# 32u4_denemesi.net
KiCad netlist of a schematic drawn in EAGLE
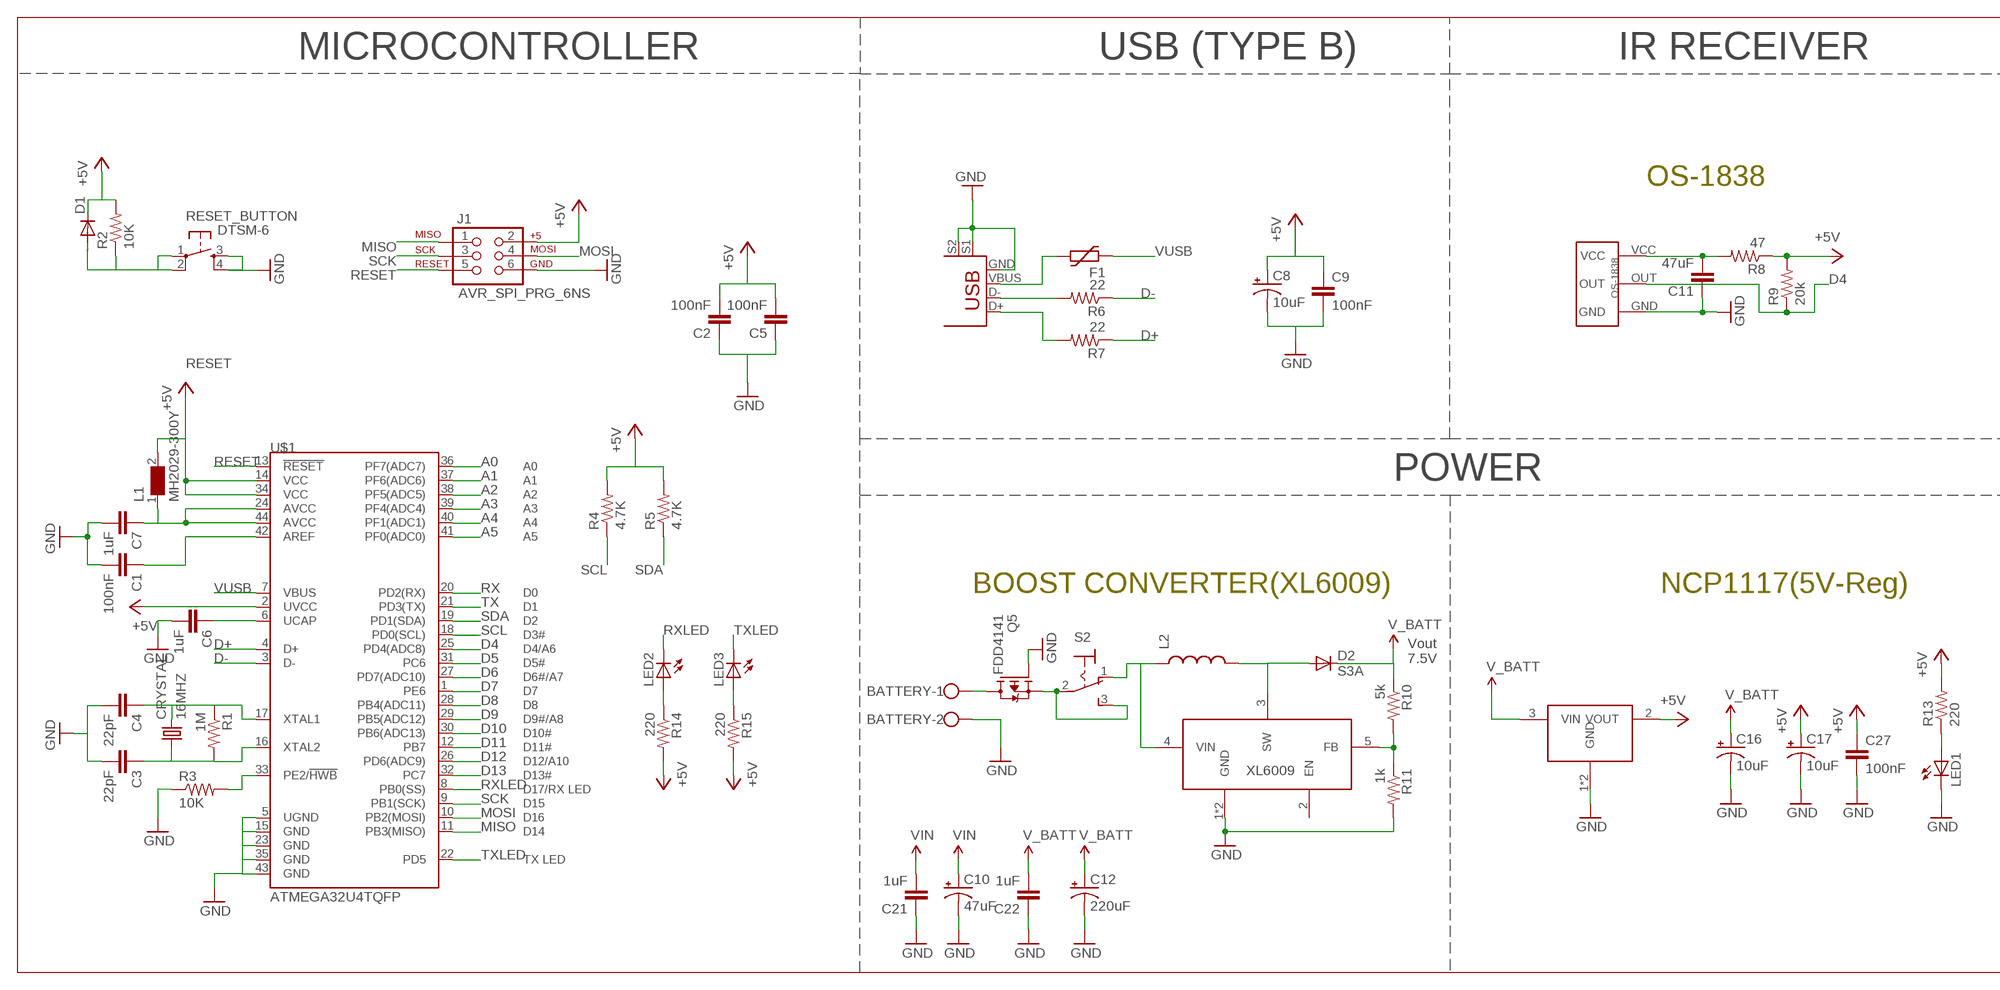
[diagram p0: schematic, sheet 1, part 1 of 2]
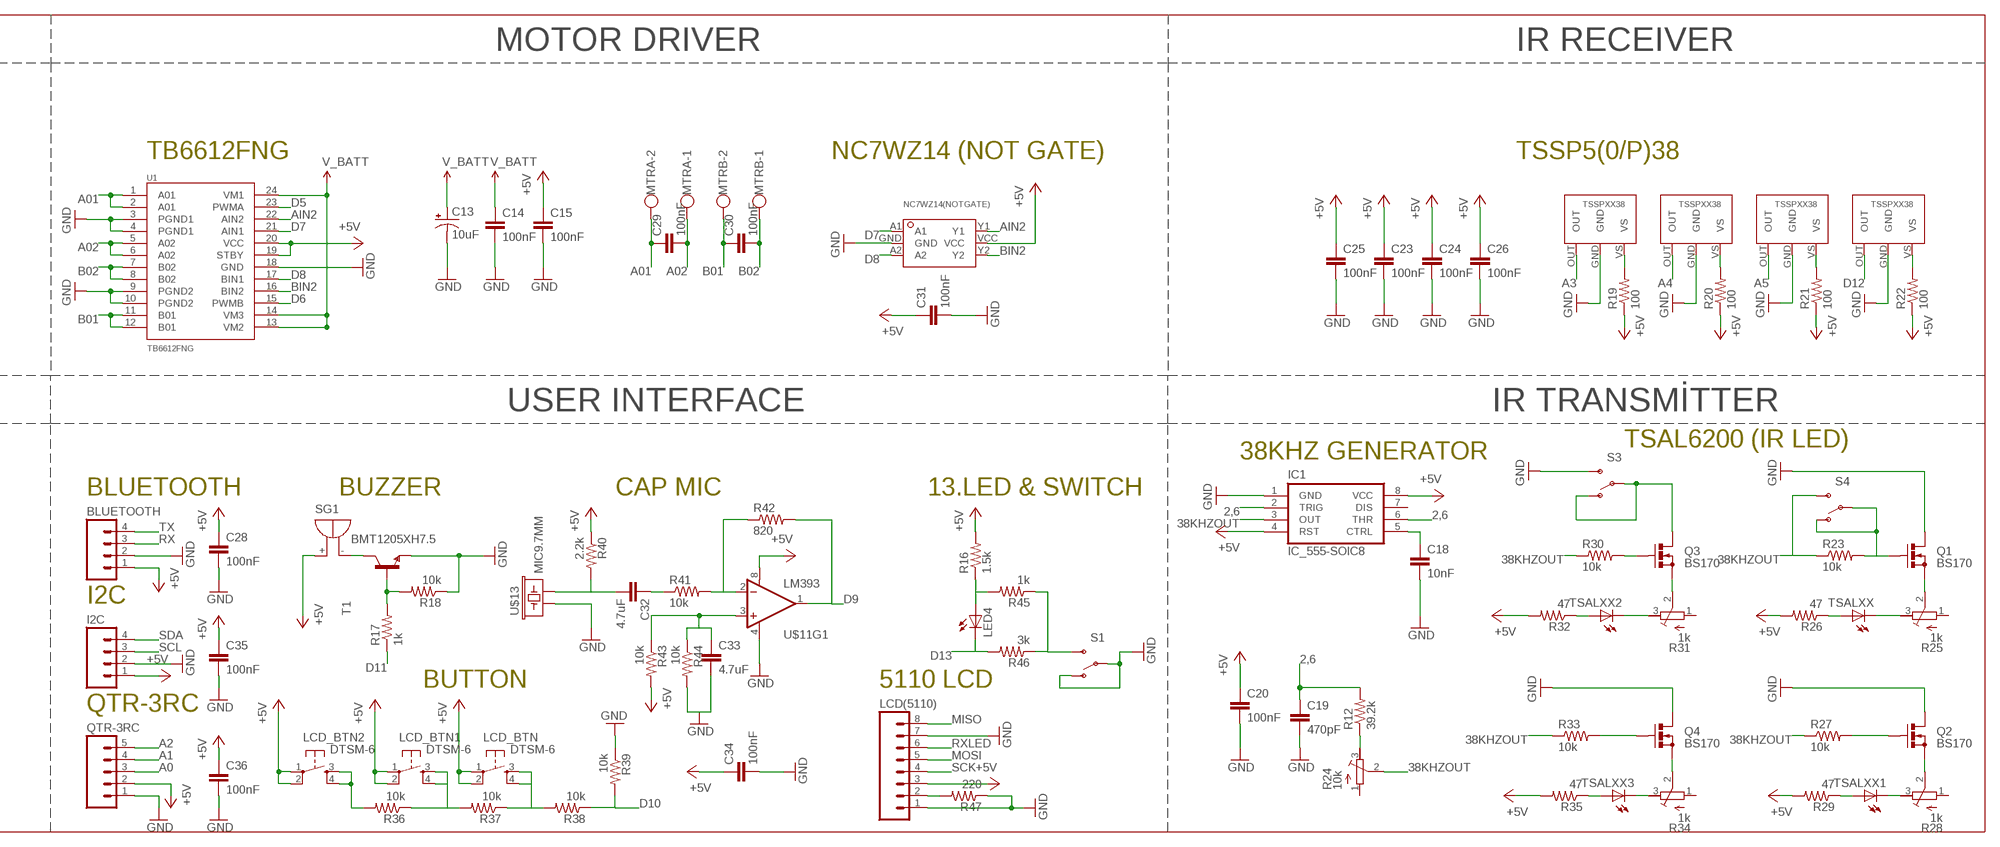
[diagram p1: schematic, sheet 1, part 2 of 2]

(export (version "E")
  (design (tool "Eeschema 10.0.6"))
  (components
    (comp (ref "BATTERY")
      (value "W237-102")
      (footprint "eagle-import:W237-102")
      (fields (field (name "MPN") "237-102"))
      (libsource (lib "eagle-import") (part "W237-102"))
    )
    (comp (ref "BLUETOOTH")
      (value "M04PTH")
      (footprint "eagle-import:1X04")
      (libsource (lib "eagle-import") (part "M04PTH"))
    )
    (comp (ref "C1")
      (value "100nF")
      (footprint "eagle-import:0805")
      (libsource (lib "eagle-import") (part "CAP0805"))
    )
    (comp (ref "C2")
      (value "100nF")
      (footprint "eagle-import:0805")
      (libsource (lib "eagle-import") (part "CAP0805"))
    )
    (comp (ref "C3")
      (value "22pF")
      (footprint "eagle-import:0805")
      (libsource (lib "eagle-import") (part "CAP0805"))
    )
    (comp (ref "C4")
      (value "22pF")
      (footprint "eagle-import:0805")
      (libsource (lib "eagle-import") (part "CAP0805"))
    )
    (comp (ref "C5")
      (value "100nF")
      (footprint "eagle-import:0805")
      (libsource (lib "eagle-import") (part "CAP0805"))
    )
    (comp (ref "C6")
      (value "1uF")
      (footprint "eagle-import:1206")
      (libsource (lib "eagle-import") (part "CAP1206"))
    )
    (comp (ref "C7")
      (value "1uF")
      (footprint "eagle-import:1206")
      (libsource (lib "eagle-import") (part "CAP1206"))
    )
    (comp (ref "C8")
      (value "10uF")
      (footprint "eagle-import:EIA3216")
      (libsource (lib "eagle-import") (part "CAP_POL1206"))
    )
    (comp (ref "C9")
      (value "100nF")
      (footprint "eagle-import:0805")
      (libsource (lib "eagle-import") (part "CAP0805"))
    )
    (comp (ref "C10")
      (value "47uF")
      (footprint "eagle-import:NIPPON_F80")
      (libsource (lib "eagle-import") (part "SparkFun-Passives_CAP_POLF80"))
    )
    (comp (ref "C11")
      (value "47uF")
      (footprint "eagle-import:1206")
      (libsource (lib "eagle-import") (part "CAP1206"))
    )
    (comp (ref "C12")
      (value "220uF")
      (footprint "eagle-import:PANASONIC_G")
      (libsource (lib "eagle-import") (part "SparkFun-Passives_CAP_POLG"))
    )
    (comp (ref "C13")
      (value "10uF")
      (footprint "eagle-import:EIA3528")
      (libsource (lib "eagle-import") (part "CAP_POL3528"))
    )
    (comp (ref "C14")
      (value "100nF")
      (footprint "eagle-import:0805")
      (libsource (lib "eagle-import") (part "CAP0805"))
    )
    (comp (ref "C15")
      (value "100nF")
      (footprint "eagle-import:0805")
      (libsource (lib "eagle-import") (part "CAP0805"))
    )
    (comp (ref "C16")
      (value "10uF")
      (footprint "eagle-import:EIA3216")
      (libsource (lib "eagle-import") (part "CAP_POL1206"))
    )
    (comp (ref "C17")
      (value "10uF")
      (footprint "eagle-import:EIA3216")
      (libsource (lib "eagle-import") (part "CAP_POL1206"))
    )
    (comp (ref "C18")
      (value "10nF")
      (footprint "eagle-import:0805")
      (libsource (lib "eagle-import") (part "CAP0805"))
    )
    (comp (ref "C19")
      (value "470pF")
      (footprint "eagle-import:0805")
      (libsource (lib "eagle-import") (part "CAP0805"))
    )
    (comp (ref "C20")
      (value "100nF")
      (footprint "eagle-import:0805")
      (libsource (lib "eagle-import") (part "CAP0805"))
    )
    (comp (ref "C21")
      (value "1uF")
      (footprint "eagle-import:1206")
      (libsource (lib "eagle-import") (part "CAP1206"))
    )
    (comp (ref "C22")
      (value "1uF")
      (footprint "eagle-import:1206")
      (libsource (lib "eagle-import") (part "CAP1206"))
    )
    (comp (ref "C23")
      (value "100nF")
      (footprint "eagle-import:0805")
      (libsource (lib "eagle-import") (part "CAP0805"))
    )
    (comp (ref "C24")
      (value "100nF")
      (footprint "eagle-import:0805")
      (libsource (lib "eagle-import") (part "CAP0805"))
    )
    (comp (ref "C25")
      (value "100nF")
      (footprint "eagle-import:0805")
      (libsource (lib "eagle-import") (part "CAP0805"))
    )
    (comp (ref "C26")
      (value "100nF")
      (footprint "eagle-import:0805")
      (libsource (lib "eagle-import") (part "CAP0805"))
    )
    (comp (ref "C27")
      (value "100nF")
      (footprint "eagle-import:0805")
      (libsource (lib "eagle-import") (part "CAP0805"))
    )
    (comp (ref "C28")
      (value "100nF")
      (footprint "eagle-import:0805")
      (libsource (lib "eagle-import") (part "CAP0805"))
    )
    (comp (ref "C29")
      (value "100nF")
      (footprint "eagle-import:0805")
      (libsource (lib "eagle-import") (part "CAP0805"))
    )
    (comp (ref "C30")
      (value "100nF")
      (footprint "eagle-import:0805")
      (libsource (lib "eagle-import") (part "CAP0805"))
    )
    (comp (ref "C31")
      (value "100nF")
      (footprint "eagle-import:0805")
      (libsource (lib "eagle-import") (part "CAP0805"))
    )
    (comp (ref "C32")
      (value "4.7uF")
      (footprint "eagle-import:1206")
      (libsource (lib "eagle-import") (part "CAP1206"))
    )
    (comp (ref "C33")
      (value "4.7uF")
      (footprint "eagle-import:1206")
      (libsource (lib "eagle-import") (part "CAP1206"))
    )
    (comp (ref "C34")
      (value "100nF")
      (footprint "eagle-import:0805")
      (libsource (lib "eagle-import") (part "CAP0805"))
    )
    (comp (ref "C35")
      (value "100nF")
      (footprint "eagle-import:0805")
      (libsource (lib "eagle-import") (part "CAP0805"))
    )
    (comp (ref "C36")
      (value "100nF")
      (footprint "eagle-import:0805")
      (libsource (lib "eagle-import") (part "CAP0805"))
    )
    (comp (ref "CRYSTAL")
      (value "16MHZ")
      (footprint "eagle-import:CRYSTAL-SMD-5X3")
      (libsource (lib "eagle-import") (part "CRYSTAL5X3"))
    )
    (comp (ref "D1")
      (value "DIODE-MINIMELF")
      (footprint "eagle-import:MINIMELF")
      (libsource (lib "eagle-import") (part "DIODE-MINIMELF"))
    )
    (comp (ref "D2")
      (value "S3A")
      (footprint "eagle-import:DO214AB")
      (fields (field (name "MF") "Fairchild"))
      (libsource (lib "eagle-import") (part "S3A"))
    )
    (comp (ref "F1")
      (value "FUSE_PTC-0805")
      (footprint "eagle-import:PTC0805")
      (libsource (lib "eagle-import") (part "FUSE_PTC-0805"))
    )
    (comp (ref "I2C")
      (value "M04PTH")
      (footprint "eagle-import:1X04")
      (libsource (lib "eagle-import") (part "M04PTH"))
    )
    (comp (ref "IC1")
      (value "IC_555-SOIC8")
      (footprint "eagle-import:SOIC-8")
      (libsource (lib "eagle-import") (part "IC_555-SOIC8"))
    )
    (comp (ref "J1")
      (value "AVR_SPI_PRG_6NS")
      (footprint "eagle-import:2X3-NS")
      (libsource (lib "eagle-import") (part "AVR_SPI_PRG_6NS"))
    )
    (comp (ref "L1")
      (value "MH2029-300Y")
      (footprint "eagle-import:0805")
      (libsource (lib "eagle-import") (part "WE-CBF_0805"))
    )
    (comp (ref "L2")
      (value "INDUCTORPWR")
      (footprint "eagle-import:CDRH125")
      (libsource (lib "eagle-import") (part "INDUCTORPWR"))
    )
    (comp (ref "LCD(5110)")
      (value "M081X08")
      (footprint "eagle-import:1X08")
      (libsource (lib "eagle-import") (part "M081X08"))
    )
    (comp (ref "LCD_BTN")
      (value "DTSM-6")
      (footprint "eagle-import:DTSM-6")
      (libsource (lib "eagle-import") (part "DTSM-6"))
    )
    (comp (ref "LCD_BTN1")
      (value "DTSM-6")
      (footprint "eagle-import:DTSM-6")
      (libsource (lib "eagle-import") (part "DTSM-6"))
    )
    (comp (ref "LCD_BTN2")
      (value "DTSM-6")
      (footprint "eagle-import:DTSM-6")
      (libsource (lib "eagle-import") (part "DTSM-6"))
    )
    (comp (ref "LED1")
      (value "LEDCHIPLED_0805")
      (footprint "eagle-import:CHIPLED_0805")
      (libsource (lib "eagle-import") (part "LEDCHIPLED_0805"))
    )
    (comp (ref "LED2")
      (value "LEDCHIPLED_0805")
      (footprint "eagle-import:CHIPLED_0805")
      (libsource (lib "eagle-import") (part "LEDCHIPLED_0805"))
    )
    (comp (ref "LED3")
      (value "LEDCHIPLED_0805")
      (footprint "eagle-import:CHIPLED_0805")
      (libsource (lib "eagle-import") (part "LEDCHIPLED_0805"))
    )
    (comp (ref "LED4")
      (value "LEDCHIPLED_0805")
      (footprint "eagle-import:CHIPLED_0805")
      (libsource (lib "eagle-import") (part "LEDCHIPLED_0805"))
    )
    (comp (ref "MTRA")
      (value "W237-102")
      (footprint "eagle-import:W237-102")
      (fields (field (name "MPN") "237-102"))
      (libsource (lib "eagle-import") (part "W237-102"))
    )
    (comp (ref "MTRB")
      (value "W237-102")
      (footprint "eagle-import:W237-102")
      (fields (field (name "MPN") "237-102"))
      (libsource (lib "eagle-import") (part "W237-102"))
    )
    (comp (ref "Q1")
      (value "BS170")
      (footprint "eagle-import:SOT54ES")
      (libsource (lib "eagle-import") (part "BS170"))
    )
    (comp (ref "Q2")
      (value "BS170")
      (footprint "eagle-import:SOT54ES")
      (libsource (lib "eagle-import") (part "BS170"))
    )
    (comp (ref "Q3")
      (value "BS170")
      (footprint "eagle-import:SOT54ES")
      (libsource (lib "eagle-import") (part "BS170"))
    )
    (comp (ref "Q4")
      (value "BS170")
      (footprint "eagle-import:SOT54ES")
      (libsource (lib "eagle-import") (part "BS170"))
    )
    (comp (ref "Q5")
      (value "FDD4141")
      (footprint "eagle-import:TO252")
      (libsource (lib "eagle-import") (part "FDD4141TO252"))
    )
    (comp (ref "QTR-3RC")
      (value "M05PTH")
      (footprint "eagle-import:1X05")
      (libsource (lib "eagle-import") (part "M05PTH"))
    )
    (comp (ref "R1")
      (value "1M")
      (footprint "eagle-import:0805")
      (libsource (lib "eagle-import") (part "SparkFun-Resistors_RESISTOR0805-RES"))
    )
    (comp (ref "R2")
      (value "10K")
      (footprint "eagle-import:0805")
      (libsource (lib "eagle-import") (part "SparkFun-Resistors_RESISTOR0805-RES"))
    )
    (comp (ref "R3")
      (value "10K")
      (footprint "eagle-import:0805")
      (libsource (lib "eagle-import") (part "SparkFun-Resistors_RESISTOR0805-RES"))
    )
    (comp (ref "R4")
      (value "4.7K")
      (footprint "eagle-import:0805")
      (libsource (lib "eagle-import") (part "SparkFun-Resistors_RESISTOR0805-RES"))
    )
    (comp (ref "R5")
      (value "4.7K")
      (footprint "eagle-import:0805")
      (libsource (lib "eagle-import") (part "SparkFun-Resistors_RESISTOR0805-RES"))
    )
    (comp (ref "R6")
      (value "22")
      (footprint "eagle-import:0805")
      (libsource (lib "eagle-import") (part "SparkFun-Resistors_RESISTOR0805-RES"))
    )
    (comp (ref "R7")
      (value "22")
      (footprint "eagle-import:0805")
      (libsource (lib "eagle-import") (part "SparkFun-Resistors_RESISTOR0805-RES"))
    )
    (comp (ref "R8")
      (value "47")
      (footprint "eagle-import:0805")
      (libsource (lib "eagle-import") (part "SparkFun-Resistors_RESISTOR0805-RES"))
    )
    (comp (ref "R9")
      (value "20k")
      (footprint "eagle-import:0805")
      (libsource (lib "eagle-import") (part "SparkFun-Resistors_RESISTOR0805-RES"))
    )
    (comp (ref "R10")
      (value "5k")
      (footprint "eagle-import:0805")
      (libsource (lib "eagle-import") (part "SparkFun-Resistors_RESISTOR0805-RES"))
    )
    (comp (ref "R11")
      (value "1k")
      (footprint "eagle-import:0805")
      (libsource (lib "eagle-import") (part "SparkFun-Resistors_RESISTOR0805-RES"))
    )
    (comp (ref "R12")
      (value "39.2k")
      (footprint "eagle-import:0402-RES")
      (libsource (lib "eagle-import") (part "RESISTOR0402-RES"))
    )
    (comp (ref "R13")
      (value "220")
      (footprint "eagle-import:0805")
      (libsource (lib "eagle-import") (part "SparkFun-Resistors_RESISTOR0805-RES"))
    )
    (comp (ref "R14")
      (value "220")
      (footprint "eagle-import:0805")
      (libsource (lib "eagle-import") (part "SparkFun-Resistors_RESISTOR0805-RES"))
    )
    (comp (ref "R15")
      (value "220")
      (footprint "eagle-import:0805")
      (libsource (lib "eagle-import") (part "SparkFun-Resistors_RESISTOR0805-RES"))
    )
    (comp (ref "R16")
      (value "1.5k")
      (footprint "eagle-import:0805")
      (libsource (lib "eagle-import") (part "SparkFun-Resistors_RESISTOR0805-RES"))
    )
    (comp (ref "R17")
      (value "1k")
      (footprint "eagle-import:0805")
      (libsource (lib "eagle-import") (part "SparkFun-Resistors_RESISTOR0805-RES"))
    )
    (comp (ref "R18")
      (value "10k")
      (footprint "eagle-import:0805")
      (libsource (lib "eagle-import") (part "SparkFun-Resistors_RESISTOR0805-RES"))
    )
    (comp (ref "R19")
      (value "100")
      (footprint "eagle-import:0805")
      (libsource (lib "eagle-import") (part "SparkFun-Resistors_RESISTOR0805-RES"))
    )
    (comp (ref "R20")
      (value "100")
      (footprint "eagle-import:0805")
      (libsource (lib "eagle-import") (part "SparkFun-Resistors_RESISTOR0805-RES"))
    )
    (comp (ref "R21")
      (value "100")
      (footprint "eagle-import:0805")
      (libsource (lib "eagle-import") (part "SparkFun-Resistors_RESISTOR0805-RES"))
    )
    (comp (ref "R22")
      (value "100")
      (footprint "eagle-import:0805")
      (libsource (lib "eagle-import") (part "SparkFun-Resistors_RESISTOR0805-RES"))
    )
    (comp (ref "R23")
      (value "10k")
      (footprint "eagle-import:0402-RES")
      (libsource (lib "eagle-import") (part "RESISTOR0402-RES"))
    )
    (comp (ref "R24")
      (value "10k")
      (footprint "eagle-import:RTRIM3296W")
      (libsource (lib "eagle-import") (part "R-TRIMM3296W"))
    )
    (comp (ref "R25")
      (value "1k")
      (footprint "eagle-import:RTRIM3296W")
      (libsource (lib "eagle-import") (part "R-TRIMM3296W"))
    )
    (comp (ref "R26")
      (value "47")
      (footprint "eagle-import:0402-RES")
      (libsource (lib "eagle-import") (part "RESISTOR0402-RES"))
    )
    (comp (ref "R27")
      (value "10k")
      (footprint "eagle-import:0402-RES")
      (libsource (lib "eagle-import") (part "RESISTOR0402-RES"))
    )
    (comp (ref "R28")
      (value "1k")
      (footprint "eagle-import:RTRIM3296W")
      (libsource (lib "eagle-import") (part "R-TRIMM3296W"))
    )
    (comp (ref "R29")
      (value "47")
      (footprint "eagle-import:0402-RES")
      (libsource (lib "eagle-import") (part "RESISTOR0402-RES"))
    )
    (comp (ref "R30")
      (value "10k")
      (footprint "eagle-import:0402-RES")
      (libsource (lib "eagle-import") (part "RESISTOR0402-RES"))
    )
    (comp (ref "R31")
      (value "1k")
      (footprint "eagle-import:RTRIM3296W")
      (libsource (lib "eagle-import") (part "R-TRIMM3296W"))
    )
    (comp (ref "R32")
      (value "47")
      (footprint "eagle-import:0402-RES")
      (libsource (lib "eagle-import") (part "RESISTOR0402-RES"))
    )
    (comp (ref "R33")
      (value "10k")
      (footprint "eagle-import:0402-RES")
      (libsource (lib "eagle-import") (part "RESISTOR0402-RES"))
    )
    (comp (ref "R34")
      (value "1k")
      (footprint "eagle-import:RTRIM3296W")
      (libsource (lib "eagle-import") (part "R-TRIMM3296W"))
    )
    (comp (ref "R35")
      (value "47")
      (footprint "eagle-import:0402-RES")
      (libsource (lib "eagle-import") (part "RESISTOR0402-RES"))
    )
    (comp (ref "R36")
      (value "10k")
      (footprint "eagle-import:0805")
      (libsource (lib "eagle-import") (part "SparkFun-Resistors_RESISTOR0805-RES"))
    )
    (comp (ref "R37")
      (value "10k")
      (footprint "eagle-import:0805")
      (libsource (lib "eagle-import") (part "SparkFun-Resistors_RESISTOR0805-RES"))
    )
    (comp (ref "R38")
      (value "10k")
      (footprint "eagle-import:0805")
      (libsource (lib "eagle-import") (part "SparkFun-Resistors_RESISTOR0805-RES"))
    )
    (comp (ref "R39")
      (value "10k")
      (footprint "eagle-import:0805")
      (libsource (lib "eagle-import") (part "SparkFun-Resistors_RESISTOR0805-RES"))
    )
    (comp (ref "R40")
      (value "2.2k")
      (footprint "eagle-import:0805")
      (libsource (lib "eagle-import") (part "SparkFun-Resistors_RESISTOR0805-RES"))
    )
    (comp (ref "R41")
      (value "10k")
      (footprint "eagle-import:0805")
      (libsource (lib "eagle-import") (part "SparkFun-Resistors_RESISTOR0805-RES"))
    )
    (comp (ref "R42")
      (value "820")
      (footprint "eagle-import:0805")
      (libsource (lib "eagle-import") (part "SparkFun-Resistors_RESISTOR0805-RES"))
    )
    (comp (ref "R43")
      (value "10k")
      (footprint "eagle-import:0805")
      (libsource (lib "eagle-import") (part "SparkFun-Resistors_RESISTOR0805-RES"))
    )
    (comp (ref "R44")
      (value "10k")
      (footprint "eagle-import:0805")
      (libsource (lib "eagle-import") (part "SparkFun-Resistors_RESISTOR0805-RES"))
    )
    (comp (ref "R45")
      (value "1k")
      (footprint "eagle-import:0805")
      (libsource (lib "eagle-import") (part "SparkFun-Resistors_RESISTOR0805-RES"))
    )
    (comp (ref "R46")
      (value "3k")
      (footprint "eagle-import:0805")
      (libsource (lib "eagle-import") (part "SparkFun-Resistors_RESISTOR0805-RES"))
    )
    (comp (ref "R47")
      (value "220")
      (footprint "eagle-import:0805")
      (libsource (lib "eagle-import") (part "SparkFun-Resistors_RESISTOR0805-RES"))
    )
    (comp (ref "RESET_BUTTON")
      (value "DTSM-6")
      (footprint "eagle-import:DTSM-6")
      (libsource (lib "eagle-import") (part "DTSM-6"))
    )
    (comp (ref "S1")
      (value "SWITCH-SPDTPTH")
      (footprint "eagle-import:SWITCH-SPDT")
      (libsource (lib "eagle-import") (part "SWITCH-SPDTPTH"))
    )
    (comp (ref "S2")
      (value "M9040P")
      (footprint "eagle-import:M9040P")
      (libsource (lib "eagle-import") (part "M9040P"))
    )
    (comp (ref "S3")
      (value "SWITCH-SPDTPTH")
      (footprint "eagle-import:SWITCH-SPDT")
      (libsource (lib "eagle-import") (part "SWITCH-SPDTPTH"))
    )
    (comp (ref "S4")
      (value "SWITCH-SPDTPTH")
      (footprint "eagle-import:SWITCH-SPDT")
      (libsource (lib "eagle-import") (part "SWITCH-SPDTPTH"))
    )
    (comp (ref "SG1")
      (value "BMT1205XH7.5")
      (footprint "eagle-import:BMT1205XH7.5")
      (libsource (lib "eagle-import") (part "BMT1205XH7.5"))
    )
    (comp (ref "T1")
      (value "MMBT2222ALT1-NPN-SOT23-BEC")
      (footprint "eagle-import:SOT23-BEC")
      (libsource (lib "eagle-import") (part "-NPN-SOT23-BECMMBT2222ALT1"))
    )
    (comp (ref "TSALXX")
      (value "LED5MM")
      (footprint "eagle-import:LED5MM")
      (libsource (lib "eagle-import") (part "LED5MM"))
    )
    (comp (ref "TSALXX1")
      (value "LED5MM")
      (footprint "eagle-import:LED5MM")
      (libsource (lib "eagle-import") (part "LED5MM"))
    )
    (comp (ref "TSALXX2")
      (value "LED5MM")
      (footprint "eagle-import:LED5MM")
      (libsource (lib "eagle-import") (part "LED5MM"))
    )
    (comp (ref "TSALXX3")
      (value "LED5MM")
      (footprint "eagle-import:LED5MM")
      (libsource (lib "eagle-import") (part "LED5MM"))
    )
    (comp (ref "U$1")
      (value "ATMEGA32U4TQFP")
      (footprint "eagle-import:SPARKFUN-DIGITALIC_TQFP44")
      (libsource (lib "eagle-import") (part "ATMEGA32U4TQFP"))
    )
    (comp (ref "U$2")
      (value "USB+SHIELD")
      (footprint "eagle-import:USB-B-PTH")
      (libsource (lib "eagle-import") (part "USB+SHIELD"))
    )
    (comp (ref "U$3")
      (value "OS-1838")
      (footprint "eagle-import:OS-1838")
      (libsource (lib "eagle-import") (part "OS-1838"))
    )
    (comp (ref "U$4")
      (value "TO263-5L")
      (footprint "eagle-import:TO263-51")
      (libsource (lib "eagle-import") (part "TO263-5L"))
    )
    (comp (ref "U$5")
      (value "NCP1117")
      (footprint "eagle-import:SOT223")
      (libsource (lib "eagle-import") (part "NCP1117"))
    )
    (comp (ref "U$6")
      (value "TSSPXX38")
      (footprint "eagle-import:TSSPXX38")
      (libsource (lib "eagle-import") (part "TSSPXX38"))
    )
    (comp (ref "U$7")
      (value "TSSPXX38")
      (footprint "eagle-import:TSSPXX38")
      (libsource (lib "eagle-import") (part "TSSPXX38"))
    )
    (comp (ref "U$8")
      (value "TSSPXX38")
      (footprint "eagle-import:TSSPXX38")
      (libsource (lib "eagle-import") (part "TSSPXX38"))
    )
    (comp (ref "U$9")
      (value "TSSPXX38")
      (footprint "eagle-import:TSSPXX38")
      (libsource (lib "eagle-import") (part "TSSPXX38"))
    )
    (comp (ref "U$10")
      (value "NC7WZ14(NOTGATE)")
      (footprint "eagle-import:SC-70-6")
      (libsource (lib "eagle-import") (part "NC7WZ14(NOTGATE)"))
    )
    (comp (ref "U$11")
      (value "LM393")
      (footprint "eagle-import:SO08")
      (libsource (lib "eagle-import") (part "LM393"))
    )
    (comp (ref "U$13")
      (value "MIC9.7MM")
      (footprint "eagle-import:MIC-9.7MM")
      (libsource (lib "eagle-import") (part "MIC9.7MM"))
    )
    (comp (ref "U1")
      (value "TB6612FNG")
      (footprint "eagle-import:SSOP24")
      (libsource (lib "eagle-import") (part "TB6621FNG"))
    )
  )
  (nets
    (net (code "1") (name "+5V") (class "Default")
      (node (ref "BLUETOOTH") (pin "1") (pinfunction "1_1") (pintype "passive"))
      (node (ref "C15") (pin "1") (pinfunction "1_1") (pintype "passive"))
      (node (ref "C17") (pin "A") (pinfunction "+_A") (pintype "passive"))
      (node (ref "C2") (pin "2") (pinfunction "2_2") (pintype "passive"))
      (node (ref "C20") (pin "1") (pinfunction "1_1") (pintype "passive"))
      (node (ref "C23") (pin "1") (pinfunction "1_1") (pintype "passive"))
      (node (ref "C24") (pin "1") (pinfunction "1_1") (pintype "passive"))
      (node (ref "C25") (pin "1") (pinfunction "1_1") (pintype "passive"))
      (node (ref "C26") (pin "1") (pinfunction "1_1") (pintype "passive"))
      (node (ref "C27") (pin "1") (pinfunction "1_1") (pintype "passive"))
      (node (ref "C28") (pin "1") (pinfunction "1_1") (pintype "passive"))
      (node (ref "C31") (pin "1") (pinfunction "1_1") (pintype "passive"))
      (node (ref "C34") (pin "1") (pinfunction "1_1") (pintype "passive"))
      (node (ref "C35") (pin "1") (pinfunction "1_1") (pintype "passive"))
      (node (ref "C36") (pin "1") (pinfunction "1_1") (pintype "passive"))
      (node (ref "C5") (pin "2") (pinfunction "2_2") (pintype "passive"))
      (node (ref "C8") (pin "A") (pinfunction "+_A") (pintype "passive"))
      (node (ref "C9") (pin "1") (pinfunction "1_1") (pintype "passive"))
      (node (ref "D1") (pin "C") (pinfunction "C_C") (pintype "passive"))
      (node (ref "I2C") (pin "1") (pinfunction "1_1") (pintype "passive"))
      (node (ref "IC1") (pin "4") (pinfunction "RST_4") (pintype "input"))
      (node (ref "IC1") (pin "8") (pinfunction "VCC_8") (pintype "power_in"))
      (node (ref "J1") (pin "2") (pinfunction "2_2") (pintype "passive"))
      (node (ref "L1") (pin "2") (pinfunction "2_2") (pintype "passive"))
      (node (ref "LCD(5110)") (pin "3") (pinfunction "3_3") (pintype "passive"))
      (node (ref "LCD_BTN") (pin "1") (pinfunction "1_1") (pintype "passive"))
      (node (ref "LCD_BTN") (pin "2") (pinfunction "2_2") (pintype "passive"))
      (node (ref "LCD_BTN1") (pin "1") (pinfunction "1_1") (pintype "passive"))
      (node (ref "LCD_BTN1") (pin "2") (pinfunction "2_2") (pintype "passive"))
      (node (ref "LCD_BTN2") (pin "1") (pinfunction "1_1") (pintype "passive"))
      (node (ref "LCD_BTN2") (pin "2") (pinfunction "2_2") (pintype "passive"))
      (node (ref "QTR-3RC") (pin "2") (pinfunction "2_2") (pintype "passive"))
      (node (ref "R13") (pin "2") (pinfunction "2_2") (pintype "passive"))
      (node (ref "R14") (pin "2") (pinfunction "2_2") (pintype "passive"))
      (node (ref "R15") (pin "2") (pinfunction "2_2") (pintype "passive"))
      (node (ref "R16") (pin "2") (pinfunction "2_2") (pintype "passive"))
      (node (ref "R19") (pin "1") (pinfunction "1_1") (pintype "passive"))
      (node (ref "R2") (pin "2") (pinfunction "2_2") (pintype "passive"))
      (node (ref "R20") (pin "1") (pinfunction "1_1") (pintype "passive"))
      (node (ref "R21") (pin "1") (pinfunction "1_1") (pintype "passive"))
      (node (ref "R22") (pin "1") (pinfunction "1_1") (pintype "passive"))
      (node (ref "R26") (pin "2") (pinfunction "2_2") (pintype "passive"))
      (node (ref "R29") (pin "2") (pinfunction "2_2") (pintype "passive"))
      (node (ref "R32") (pin "2") (pinfunction "2_2") (pintype "passive"))
      (node (ref "R35") (pin "2") (pinfunction "2_2") (pintype "passive"))
      (node (ref "R4") (pin "2") (pinfunction "2_2") (pintype "passive"))
      (node (ref "R40") (pin "1") (pinfunction "1_1") (pintype "passive"))
      (node (ref "R43") (pin "2") (pinfunction "2_2") (pintype "passive"))
      (node (ref "R5") (pin "2") (pinfunction "2_2") (pintype "passive"))
      (node (ref "R8") (pin "1") (pinfunction "1_1") (pintype "passive"))
      (node (ref "R9") (pin "2") (pinfunction "2_2") (pintype "passive"))
      (node (ref "SG1") (pin "+") (pinfunction "+_+") (pintype "passive"))
      (node (ref "U$1") (pin "14") (pinfunction "VCC_14") (pintype "bidirectional"))
      (node (ref "U$1") (pin "2") (pinfunction "UVCC_2") (pintype "bidirectional"))
      (node (ref "U$1") (pin "34") (pinfunction "VCC_34") (pintype "bidirectional"))
      (node (ref "U$10") (pin "VCC") (pinfunction "VCC_VCC") (pintype "bidirectional"))
      (node (ref "U$11") (pin "8") (pinfunction "V+_8") (pintype "power_in"))
      (node (ref "U$5") (pin "2") (pinfunction "VOUT_2") (pintype "bidirectional"))
      (node (ref "U1") (pin "19") (pinfunction "STBY_19") (pintype "bidirectional"))
      (node (ref "U1") (pin "20") (pinfunction "VCC_20") (pintype "bidirectional"))
    )
    (net (code "2") (name "/2,6") (class "Default")
      (node (ref "C19") (pin "1") (pinfunction "1_1") (pintype "passive"))
      (node (ref "IC1") (pin "2") (pinfunction "TRIG_2") (pintype "input"))
      (node (ref "IC1") (pin "6") (pinfunction "THR_6") (pintype "input"))
      (node (ref "R12") (pin "2") (pinfunction "2_2") (pintype "passive"))
    )
    (net (code "3") (name "/38KHZOUT") (class "Default")
      (node (ref "IC1") (pin "3") (pinfunction "OUT_3") (pintype "output"))
      (node (ref "R23") (pin "1") (pinfunction "1_1") (pintype "passive"))
      (node (ref "R24") (pin "2") (pinfunction "S_2") (pintype "passive"))
      (node (ref "R27") (pin "1") (pinfunction "1_1") (pintype "passive"))
      (node (ref "R30") (pin "1") (pinfunction "1_1") (pintype "passive"))
      (node (ref "R33") (pin "1") (pinfunction "1_1") (pintype "passive"))
      (node (ref "S4") (pin "3") (pinfunction "S_3") (pintype "passive"))
    )
    (net (code "4") (name "/A0") (class "Default")
      (node (ref "QTR-3RC") (pin "3") (pinfunction "3_3") (pintype "passive"))
      (node (ref "U$1") (pin "36") (pinfunction "PF7(ADC7)_36") (pintype "bidirectional"))
    )
    (net (code "5") (name "/A1") (class "Default")
      (node (ref "QTR-3RC") (pin "4") (pinfunction "4_4") (pintype "passive"))
      (node (ref "U$1") (pin "37") (pinfunction "PF6(ADC6)_37") (pintype "bidirectional"))
    )
    (net (code "6") (name "/A01") (class "Default")
      (node (ref "C29") (pin "1") (pinfunction "1_1") (pintype "passive"))
      (node (ref "MTRA") (pin "2") (pinfunction "KL_2") (pintype "passive"))
      (node (ref "U1") (pin "1") (pinfunction "A01_1") (pintype "bidirectional"))
      (node (ref "U1") (pin "2") (pinfunction "A01_2") (pintype "bidirectional"))
    )
    (net (code "7") (name "/A2") (class "Default")
      (node (ref "QTR-3RC") (pin "5") (pinfunction "5_5") (pintype "passive"))
      (node (ref "U$1") (pin "38") (pinfunction "PF5(ADC5)_38") (pintype "bidirectional"))
    )
    (net (code "8") (name "/A02") (class "Default")
      (node (ref "C29") (pin "2") (pinfunction "2_2") (pintype "passive"))
      (node (ref "MTRA") (pin "1") (pinfunction "KL_1") (pintype "passive"))
      (node (ref "U1") (pin "5") (pinfunction "A02_5") (pintype "bidirectional"))
      (node (ref "U1") (pin "6") (pinfunction "A02_6") (pintype "bidirectional"))
    )
    (net (code "9") (name "/A3") (class "Default")
      (node (ref "U$1") (pin "39") (pinfunction "PF4(ADC4)_39") (pintype "bidirectional"))
      (node (ref "U$9") (pin "OUT") (pinfunction "OUT_OUT") (pintype "bidirectional"))
    )
    (net (code "10") (name "/A4") (class "Default")
      (node (ref "U$1") (pin "40") (pinfunction "PF1(ADC1)_40") (pintype "bidirectional"))
      (node (ref "U$8") (pin "OUT") (pinfunction "OUT_OUT") (pintype "bidirectional"))
    )
    (net (code "11") (name "/A5") (class "Default")
      (node (ref "U$1") (pin "41") (pinfunction "PF0(ADC0)_41") (pintype "bidirectional"))
      (node (ref "U$7") (pin "OUT") (pinfunction "OUT_OUT") (pintype "bidirectional"))
    )
    (net (code "12") (name "/AIN2") (class "Default")
      (node (ref "U$10") (pin "Y1") (pinfunction "Y1_Y1") (pintype "bidirectional"))
      (node (ref "U1") (pin "22") (pinfunction "AIN2_22") (pintype "bidirectional"))
    )
    (net (code "13") (name "/B01") (class "Default")
      (node (ref "C30") (pin "1") (pinfunction "1_1") (pintype "passive"))
      (node (ref "MTRB") (pin "2") (pinfunction "KL_2") (pintype "passive"))
      (node (ref "U1") (pin "11") (pinfunction "B01_11") (pintype "bidirectional"))
      (node (ref "U1") (pin "12") (pinfunction "B01_12") (pintype "bidirectional"))
    )
    (net (code "14") (name "/B02") (class "Default")
      (node (ref "C30") (pin "2") (pinfunction "2_2") (pintype "passive"))
      (node (ref "MTRB") (pin "1") (pinfunction "KL_1") (pintype "passive"))
      (node (ref "U1") (pin "7") (pinfunction "B02_7") (pintype "bidirectional"))
      (node (ref "U1") (pin "8") (pinfunction "B02_8") (pintype "bidirectional"))
    )
    (net (code "15") (name "/BIN2") (class "Default")
      (node (ref "U$10") (pin "Y2") (pinfunction "Y2_Y2") (pintype "bidirectional"))
      (node (ref "U1") (pin "16") (pinfunction "BIN2_16") (pintype "bidirectional"))
    )
    (net (code "16") (name "/D+") (class "Default")
      (node (ref "R7") (pin "1") (pinfunction "1_1") (pintype "passive"))
      (node (ref "U$1") (pin "4") (pinfunction "D+_4") (pintype "bidirectional"))
    )
    (net (code "17") (name "/D-") (class "Default")
      (node (ref "R6") (pin "1") (pinfunction "1_1") (pintype "passive"))
      (node (ref "U$1") (pin "3") (pinfunction "D-_3") (pintype "bidirectional"))
    )
    (net (code "18") (name "/D4") (class "Default")
      (node (ref "R9") (pin "1") (pinfunction "1_1") (pintype "passive"))
      (node (ref "U$1") (pin "25") (pinfunction "PD4(ADC8)_25") (pintype "bidirectional"))
      (node (ref "U$3") (pin "OUT") (pinfunction "OUT_OUT") (pintype "bidirectional"))
    )
    (net (code "19") (name "/D5") (class "Default")
      (node (ref "U$1") (pin "31") (pinfunction "PC6_31") (pintype "bidirectional"))
      (node (ref "U1") (pin "23") (pinfunction "PWMA_23") (pintype "bidirectional"))
    )
    (net (code "20") (name "/D6") (class "Default")
      (node (ref "U$1") (pin "27") (pinfunction "PD7(ADC10)_27") (pintype "bidirectional"))
      (node (ref "U1") (pin "15") (pinfunction "PWMB_15") (pintype "bidirectional"))
    )
    (net (code "21") (name "/D7") (class "Default")
      (node (ref "U$1") (pin "1") (pinfunction "PE6_1") (pintype "bidirectional"))
      (node (ref "U$10") (pin "A1") (pinfunction "A1_A1") (pintype "bidirectional"))
      (node (ref "U1") (pin "21") (pinfunction "AIN1_21") (pintype "bidirectional"))
    )
    (net (code "22") (name "/D8") (class "Default")
      (node (ref "U$1") (pin "28") (pinfunction "PB4(ADC11)_28") (pintype "bidirectional"))
      (node (ref "U$10") (pin "A2") (pinfunction "A2_A2") (pintype "bidirectional"))
      (node (ref "U1") (pin "17") (pinfunction "BIN1_17") (pintype "bidirectional"))
    )
    (net (code "23") (name "/D9") (class "Default")
      (node (ref "R42") (pin "2") (pinfunction "2_2") (pintype "passive"))
      (node (ref "U$1") (pin "29") (pinfunction "PB5(ADC12)_29") (pintype "bidirectional"))
      (node (ref "U$11") (pin "1") (pinfunction "OUT_1") (pintype "output"))
    )
    (net (code "24") (name "/D10") (class "Default")
      (node (ref "R38") (pin "1") (pinfunction "1_1") (pintype "passive"))
      (node (ref "R39") (pin "2") (pinfunction "2_2") (pintype "passive"))
      (node (ref "U$1") (pin "30") (pinfunction "PB6(ADC13)_30") (pintype "bidirectional"))
    )
    (net (code "25") (name "/D11") (class "Default")
      (node (ref "R17") (pin "1") (pinfunction "1_1") (pintype "passive"))
      (node (ref "U$1") (pin "12") (pinfunction "PB7_12") (pintype "bidirectional"))
    )
    (net (code "26") (name "/D12") (class "Default")
      (node (ref "U$1") (pin "26") (pinfunction "PD6(ADC9)_26") (pintype "bidirectional"))
      (node (ref "U$6") (pin "OUT") (pinfunction "OUT_OUT") (pintype "bidirectional"))
    )
    (net (code "27") (name "/D13") (class "Default")
      (node (ref "LED4") (pin "C") (pinfunction "C_C") (pintype "passive"))
      (node (ref "R46") (pin "2") (pinfunction "2_2") (pintype "passive"))
      (node (ref "U$1") (pin "32") (pinfunction "PC7_32") (pintype "bidirectional"))
    )
    (net (code "28") (name "/MISO") (class "Default")
      (node (ref "J1") (pin "1") (pinfunction "1_1") (pintype "passive"))
      (node (ref "LCD(5110)") (pin "8") (pinfunction "8_8") (pintype "passive"))
      (node (ref "U$1") (pin "11") (pinfunction "PB3(MISO)_11") (pintype "bidirectional"))
    )
    (net (code "29") (name "/MOSI") (class "Default")
      (node (ref "J1") (pin "4") (pinfunction "4_4") (pintype "passive"))
      (node (ref "LCD(5110)") (pin "5") (pinfunction "5_5") (pintype "passive"))
      (node (ref "U$1") (pin "10") (pinfunction "PB2(MOSI)_10") (pintype "bidirectional"))
    )
    (net (code "30") (name "/RESET") (class "Default")
      (node (ref "D1") (pin "A") (pinfunction "A_A") (pintype "passive"))
      (node (ref "J1") (pin "5") (pinfunction "5_5") (pintype "passive"))
      (node (ref "R2") (pin "1") (pinfunction "1_1") (pintype "passive"))
      (node (ref "RESET_BUTTON") (pin "1") (pinfunction "1_1") (pintype "passive"))
      (node (ref "RESET_BUTTON") (pin "2") (pinfunction "2_2") (pintype "passive"))
      (node (ref "U$1") (pin "13") (pinfunction "~{RESET}_13") (pintype "bidirectional"))
    )
    (net (code "31") (name "/RX") (class "Default")
      (node (ref "BLUETOOTH") (pin "3") (pinfunction "3_3") (pintype "passive"))
      (node (ref "U$1") (pin "20") (pinfunction "PD2(RX)_20") (pintype "bidirectional"))
    )
    (net (code "32") (name "/RXLED") (class "Default")
      (node (ref "LCD(5110)") (pin "6") (pinfunction "6_6") (pintype "passive"))
      (node (ref "LED2") (pin "C") (pinfunction "C_C") (pintype "passive"))
      (node (ref "U$1") (pin "8") (pinfunction "PB0(SS)_8") (pintype "bidirectional"))
    )
    (net (code "33") (name "/SCK") (class "Default")
      (node (ref "J1") (pin "3") (pinfunction "3_3") (pintype "passive"))
      (node (ref "LCD(5110)") (pin "4") (pinfunction "4_4") (pintype "passive"))
      (node (ref "U$1") (pin "9") (pinfunction "PB1(SCK)_9") (pintype "bidirectional"))
    )
    (net (code "34") (name "/SCL") (class "Default")
      (node (ref "I2C") (pin "3") (pinfunction "3_3") (pintype "passive"))
      (node (ref "R4") (pin "1") (pinfunction "1_1") (pintype "passive"))
      (node (ref "U$1") (pin "18") (pinfunction "PD0(SCL)_18") (pintype "bidirectional"))
    )
    (net (code "35") (name "/SDA") (class "Default")
      (node (ref "I2C") (pin "4") (pinfunction "4_4") (pintype "passive"))
      (node (ref "R5") (pin "1") (pinfunction "1_1") (pintype "passive"))
      (node (ref "U$1") (pin "19") (pinfunction "PD1(SDA)_19") (pintype "bidirectional"))
    )
    (net (code "36") (name "/TX") (class "Default")
      (node (ref "BLUETOOTH") (pin "4") (pinfunction "4_4") (pintype "passive"))
      (node (ref "U$1") (pin "21") (pinfunction "PD3(TX)_21") (pintype "bidirectional"))
    )
    (net (code "37") (name "/TXLED") (class "Default")
      (node (ref "LED3") (pin "C") (pinfunction "C_C") (pintype "passive"))
      (node (ref "U$1") (pin "22") (pinfunction "PD5_22") (pintype "bidirectional"))
    )
    (net (code "38") (name "/VUSB") (class "Default")
      (node (ref "F1") (pin "1") (pinfunction "1_1") (pintype "passive"))
      (node (ref "U$1") (pin "7") (pinfunction "VBUS_7") (pintype "bidirectional"))
    )
    (net (code "39") (name "GND") (class "Default")
      (node (ref "BATTERY") (pin "2") (pinfunction "KL_2") (pintype "passive"))
      (node (ref "BLUETOOTH") (pin "2") (pinfunction "2_2") (pintype "passive"))
      (node (ref "C1") (pin "2") (pinfunction "2_2") (pintype "passive"))
      (node (ref "C10") (pin "-") (pinfunction "-_-") (pintype "passive"))
      (node (ref "C11") (pin "1") (pinfunction "1_1") (pintype "passive"))
      (node (ref "C12") (pin "-") (pinfunction "-_-") (pintype "passive"))
      (node (ref "C13") (pin "C") (pinfunction "-_C") (pintype "passive"))
      (node (ref "C14") (pin "2") (pinfunction "2_2") (pintype "passive"))
      (node (ref "C15") (pin "2") (pinfunction "2_2") (pintype "passive"))
      (node (ref "C16") (pin "C") (pinfunction "-_C") (pintype "passive"))
      (node (ref "C17") (pin "C") (pinfunction "-_C") (pintype "passive"))
      (node (ref "C18") (pin "2") (pinfunction "2_2") (pintype "passive"))
      (node (ref "C19") (pin "2") (pinfunction "2_2") (pintype "passive"))
      (node (ref "C2") (pin "1") (pinfunction "1_1") (pintype "passive"))
      (node (ref "C20") (pin "2") (pinfunction "2_2") (pintype "passive"))
      (node (ref "C21") (pin "1") (pinfunction "1_1") (pintype "passive"))
      (node (ref "C22") (pin "1") (pinfunction "1_1") (pintype "passive"))
      (node (ref "C23") (pin "2") (pinfunction "2_2") (pintype "passive"))
      (node (ref "C24") (pin "2") (pinfunction "2_2") (pintype "passive"))
      (node (ref "C25") (pin "2") (pinfunction "2_2") (pintype "passive"))
      (node (ref "C26") (pin "2") (pinfunction "2_2") (pintype "passive"))
      (node (ref "C27") (pin "2") (pinfunction "2_2") (pintype "passive"))
      (node (ref "C28") (pin "2") (pinfunction "2_2") (pintype "passive"))
      (node (ref "C3") (pin "2") (pinfunction "2_2") (pintype "passive"))
      (node (ref "C31") (pin "2") (pinfunction "2_2") (pintype "passive"))
      (node (ref "C33") (pin "2") (pinfunction "2_2") (pintype "passive"))
      (node (ref "C34") (pin "2") (pinfunction "2_2") (pintype "passive"))
      (node (ref "C35") (pin "2") (pinfunction "2_2") (pintype "passive"))
      (node (ref "C36") (pin "2") (pinfunction "2_2") (pintype "passive"))
      (node (ref "C4") (pin "2") (pinfunction "2_2") (pintype "passive"))
      (node (ref "C5") (pin "1") (pinfunction "1_1") (pintype "passive"))
      (node (ref "C6") (pin "2") (pinfunction "2_2") (pintype "passive"))
      (node (ref "C7") (pin "2") (pinfunction "2_2") (pintype "passive"))
      (node (ref "C8") (pin "C") (pinfunction "-_C") (pintype "passive"))
      (node (ref "C9") (pin "2") (pinfunction "2_2") (pintype "passive"))
      (node (ref "I2C") (pin "2") (pinfunction "2_2") (pintype "passive"))
      (node (ref "IC1") (pin "1") (pinfunction "GND_1") (pintype "power_in"))
      (node (ref "J1") (pin "6") (pinfunction "6_6") (pintype "passive"))
      (node (ref "LCD(5110)") (pin "1") (pinfunction "1_1") (pintype "passive"))
      (node (ref "LCD(5110)") (pin "7") (pinfunction "7_7") (pintype "passive"))
      (node (ref "LED1") (pin "C") (pinfunction "C_C") (pintype "passive"))
      (node (ref "Q1") (pin "D") (pinfunction "D_D") (pintype "passive"))
      (node (ref "Q2") (pin "D") (pinfunction "D_D") (pintype "passive"))
      (node (ref "Q4") (pin "D") (pinfunction "D_D") (pintype "passive"))
      (node (ref "Q5") (pin "1") (pinfunction "G_1") (pintype "passive"))
      (node (ref "QTR-3RC") (pin "1") (pinfunction "1_1") (pintype "passive"))
      (node (ref "R11") (pin "2") (pinfunction "2_2") (pintype "passive"))
      (node (ref "R18") (pin "1") (pinfunction "1_1") (pintype "passive"))
      (node (ref "R3") (pin "1") (pinfunction "1_1") (pintype "passive"))
      (node (ref "R39") (pin "1") (pinfunction "1_1") (pintype "passive"))
      (node (ref "R44") (pin "2") (pinfunction "2_2") (pintype "passive"))
      (node (ref "R47") (pin "1") (pinfunction "1_1") (pintype "passive"))
      (node (ref "RESET_BUTTON") (pin "3") (pinfunction "3_3") (pintype "passive"))
      (node (ref "RESET_BUTTON") (pin "4") (pinfunction "4_4") (pintype "passive"))
      (node (ref "S1") (pin "1") (pinfunction "O_1") (pintype "passive"))
      (node (ref "S1") (pin "2") (pinfunction "P_2") (pintype "passive"))
      (node (ref "S3") (pin "3") (pinfunction "S_3") (pintype "passive"))
      (node (ref "T1") (pin "E") (pinfunction "E_E") (pintype "passive"))
      (node (ref "U$1") (pin "15") (pinfunction "GND_15") (pintype "bidirectional"))
      (node (ref "U$1") (pin "23") (pinfunction "GND_23") (pintype "bidirectional"))
      (node (ref "U$1") (pin "35") (pinfunction "GND_35") (pintype "bidirectional"))
      (node (ref "U$1") (pin "43") (pinfunction "GND_43") (pintype "bidirectional"))
      (node (ref "U$1") (pin "5") (pinfunction "UGND_5") (pintype "bidirectional"))
      (node (ref "U$10") (pin "GND") (pinfunction "GND_GND") (pintype "bidirectional"))
      (node (ref "U$11") (pin "4") (pinfunction "V-_4") (pintype "power_in"))
      (node (ref "U$13") (pin "1") (pinfunction "1_1") (pintype "passive"))
      (node (ref "U$2") (pin "GND") (pinfunction "GND_GND") (pintype "bidirectional"))
      (node (ref "U$2") (pin "S1") (pinfunction "S1_S1") (pintype "bidirectional"))
      (node (ref "U$2") (pin "S2") (pinfunction "S2_S2") (pintype "bidirectional"))
      (node (ref "U$3") (pin "GND") (pinfunction "GND_GND") (pintype "bidirectional"))
      (node (ref "U$4") (pin "1") (pinfunction "GND_1") (pintype "bidirectional"))
      (node (ref "U$4") (pin "6") (pinfunction "GND_6") (pintype "bidirectional"))
      (node (ref "U$5") (pin "1") (pinfunction "GND_1") (pintype "bidirectional"))
      (node (ref "U$5") (pin "4") (pinfunction "GND_4") (pintype "bidirectional"))
      (node (ref "U$6") (pin "GND") (pinfunction "GND_GND") (pintype "bidirectional"))
      (node (ref "U$7") (pin "GND") (pinfunction "GND_GND") (pintype "bidirectional"))
      (node (ref "U$8") (pin "GND") (pinfunction "GND_GND") (pintype "bidirectional"))
      (node (ref "U$9") (pin "GND") (pinfunction "GND_GND") (pintype "bidirectional"))
      (node (ref "U1") (pin "10") (pinfunction "PGND2_10") (pintype "bidirectional"))
      (node (ref "U1") (pin "18") (pinfunction "GND_18") (pintype "bidirectional"))
      (node (ref "U1") (pin "3") (pinfunction "PGND1_3") (pintype "bidirectional"))
      (node (ref "U1") (pin "4") (pinfunction "PGND1_4") (pintype "bidirectional"))
      (node (ref "U1") (pin "9") (pinfunction "PGND2_9") (pintype "bidirectional"))
    )
    (net (code "40") (name "Net-(BATTERYA-KL)") (class "Default")
      (node (ref "BATTERY") (pin "1") (pinfunction "KL_1") (pintype "passive"))
      (node (ref "Q5") (pin "3") (pinfunction "D_3") (pintype "passive"))
    )
    (net (code "41") (name "Net-(C7-Pad1)") (class "Default")
      (node (ref "C7") (pin "1") (pinfunction "1_1") (pintype "passive"))
      (node (ref "L1") (pin "1") (pinfunction "1_1") (pintype "passive"))
      (node (ref "U$1") (pin "24") (pinfunction "AVCC_24") (pintype "bidirectional"))
      (node (ref "U$1") (pin "44") (pinfunction "AVCC_44") (pintype "bidirectional"))
    )
    (net (code "42") (name "Net-(C11-Pad2)") (class "Default")
      (node (ref "C11") (pin "2") (pinfunction "2_2") (pintype "passive"))
      (node (ref "R8") (pin "2") (pinfunction "2_2") (pintype "passive"))
      (node (ref "U$3") (pin "VCC") (pinfunction "VCC_VCC") (pintype "bidirectional"))
    )
    (net (code "43") (name "Net-(C32-Pad1)") (class "Default")
      (node (ref "C32") (pin "1") (pinfunction "1_1") (pintype "passive"))
      (node (ref "R41") (pin "1") (pinfunction "1_1") (pintype "passive"))
    )
    (net (code "44") (name "Net-(C32-Pad2)") (class "Default")
      (node (ref "C32") (pin "2") (pinfunction "2_2") (pintype "passive"))
      (node (ref "R40") (pin "2") (pinfunction "2_2") (pintype "passive"))
      (node (ref "U$13") (pin "2") (pinfunction "2_2") (pintype "passive"))
    )
    (net (code "45") (name "Net-(CRYSTAL-2)") (class "Default")
      (node (ref "C4") (pin "1") (pinfunction "1_1") (pintype "passive"))
      (node (ref "CRYSTAL") (pin "3") (pinfunction "2_3") (pintype "passive"))
      (node (ref "R1") (pin "1") (pinfunction "1_1") (pintype "passive"))
      (node (ref "U$1") (pin "17") (pinfunction "XTAL1_17") (pintype "bidirectional"))
    )
    (net (code "46") (name "Net-(F1-Pad2)") (class "Default")
      (node (ref "F1") (pin "2") (pinfunction "2_2") (pintype "passive"))
      (node (ref "U$2") (pin "VBUS") (pinfunction "VBUS_VBUS") (pintype "bidirectional"))
    )
    (net (code "47") (name "Net-(IC1-CTRL)") (class "Default")
      (node (ref "C18") (pin "1") (pinfunction "1_1") (pintype "passive"))
      (node (ref "IC1") (pin "5") (pinfunction "CTRL_5") (pintype "power_in"))
    )
    (net (code "48") (name "Net-(LCD(5110)-Pad2)") (class "Default")
      (node (ref "LCD(5110)") (pin "2") (pinfunction "2_2") (pintype "passive"))
      (node (ref "R47") (pin "2") (pinfunction "2_2") (pintype "passive"))
    )
    (net (code "49") (name "Net-(LCD_BTN-Pad3)") (class "Default")
      (node (ref "LCD_BTN") (pin "3") (pinfunction "3_3") (pintype "passive"))
      (node (ref "LCD_BTN") (pin "4") (pinfunction "4_4") (pintype "passive"))
      (node (ref "R37") (pin "1") (pinfunction "1_1") (pintype "passive"))
      (node (ref "R38") (pin "2") (pinfunction "2_2") (pintype "passive"))
    )
    (net (code "50") (name "Net-(LCD_BTN1-Pad3)") (class "Default")
      (node (ref "LCD_BTN1") (pin "3") (pinfunction "3_3") (pintype "passive"))
      (node (ref "LCD_BTN1") (pin "4") (pinfunction "4_4") (pintype "passive"))
      (node (ref "R36") (pin "1") (pinfunction "1_1") (pintype "passive"))
      (node (ref "R37") (pin "2") (pinfunction "2_2") (pintype "passive"))
    )
    (net (code "51") (name "Net-(LCD_BTN2-Pad3)") (class "Default")
      (node (ref "LCD_BTN2") (pin "3") (pinfunction "3_3") (pintype "passive"))
      (node (ref "LCD_BTN2") (pin "4") (pinfunction "4_4") (pintype "passive"))
      (node (ref "R36") (pin "2") (pinfunction "2_2") (pintype "passive"))
    )
    (net (code "52") (name "Net-(LED1-PadA)") (class "Default")
      (node (ref "LED1") (pin "A") (pinfunction "A_A") (pintype "passive"))
      (node (ref "R13") (pin "1") (pinfunction "1_1") (pintype "passive"))
    )
    (net (code "53") (name "Net-(LED2-PadA)") (class "Default")
      (node (ref "LED2") (pin "A") (pinfunction "A_A") (pintype "passive"))
      (node (ref "R14") (pin "1") (pinfunction "1_1") (pintype "passive"))
    )
    (net (code "54") (name "Net-(LED3-PadA)") (class "Default")
      (node (ref "LED3") (pin "A") (pinfunction "A_A") (pintype "passive"))
      (node (ref "R15") (pin "1") (pinfunction "1_1") (pintype "passive"))
    )
    (net (code "55") (name "Net-(LED4-PadA)") (class "Default")
      (node (ref "LED4") (pin "A") (pinfunction "A_A") (pintype "passive"))
      (node (ref "R16") (pin "1") (pinfunction "1_1") (pintype "passive"))
      (node (ref "R45") (pin "2") (pinfunction "2_2") (pintype "passive"))
    )
    (net (code "56") (name "Net-(Q2-PadG)") (class "Default")
      (node (ref "Q2") (pin "G") (pinfunction "G_G") (pintype "passive"))
      (node (ref "R27") (pin "2") (pinfunction "2_2") (pintype "passive"))
    )
    (net (code "57") (name "Net-(Q3-PadG)") (class "Default")
      (node (ref "Q3") (pin "G") (pinfunction "G_G") (pintype "passive"))
      (node (ref "R30") (pin "2") (pinfunction "2_2") (pintype "passive"))
    )
    (net (code "58") (name "Net-(Q4-PadG)") (class "Default")
      (node (ref "Q4") (pin "G") (pinfunction "G_G") (pintype "passive"))
      (node (ref "R33") (pin "2") (pinfunction "2_2") (pintype "passive"))
    )
    (net (code "59") (name "Net-(Q5-S)") (class "Default")
      (node (ref "Q5") (pin "2") (pinfunction "S_2") (pintype "passive"))
      (node (ref "S2") (pin "2") (pinfunction "P_2") (pintype "passive"))
      (node (ref "S2") (pin "3") (pinfunction "S_3") (pintype "passive"))
    )
    (net (code "60") (name "Net-(R6-Pad2)") (class "Default")
      (node (ref "R6") (pin "2") (pinfunction "2_2") (pintype "passive"))
      (node (ref "U$2") (pin "D-") (pinfunction "D-_D-") (pintype "bidirectional"))
    )
    (net (code "61") (name "Net-(R7-Pad2)") (class "Default")
      (node (ref "R7") (pin "2") (pinfunction "2_2") (pintype "passive"))
      (node (ref "U$2") (pin "D+") (pinfunction "D+_D+") (pintype "bidirectional"))
    )
    (net (code "62") (name "Net-(R17-Pad2)") (class "Default")
      (node (ref "R17") (pin "2") (pinfunction "2_2") (pintype "passive"))
      (node (ref "R18") (pin "2") (pinfunction "2_2") (pintype "passive"))
      (node (ref "T1") (pin "B") (pinfunction "B_B") (pintype "passive"))
    )
    (net (code "63") (name "Net-(R19-Pad2)") (class "Default")
      (node (ref "R19") (pin "2") (pinfunction "2_2") (pintype "passive"))
      (node (ref "U$9") (pin "VS") (pinfunction "VS_VS") (pintype "bidirectional"))
    )
    (net (code "64") (name "Net-(R20-Pad2)") (class "Default")
      (node (ref "R20") (pin "2") (pinfunction "2_2") (pintype "passive"))
      (node (ref "U$8") (pin "VS") (pinfunction "VS_VS") (pintype "bidirectional"))
    )
    (net (code "65") (name "Net-(R21-Pad2)") (class "Default")
      (node (ref "R21") (pin "2") (pinfunction "2_2") (pintype "passive"))
      (node (ref "U$7") (pin "VS") (pinfunction "VS_VS") (pintype "bidirectional"))
    )
    (net (code "66") (name "Net-(R22-Pad2)") (class "Default")
      (node (ref "R22") (pin "2") (pinfunction "2_2") (pintype "passive"))
      (node (ref "U$6") (pin "VS") (pinfunction "VS_VS") (pintype "bidirectional"))
    )
    (net (code "67") (name "Net-(R24-A)") (class "Default")
      (node (ref "R12") (pin "1") (pinfunction "1_1") (pintype "passive"))
      (node (ref "R24") (pin "3") (pinfunction "A_3") (pintype "passive"))
    )
    (net (code "68") (name "Net-(R25-A)") (class "Default")
      (node (ref "R25") (pin "3") (pinfunction "A_3") (pintype "passive"))
      (node (ref "TSALXX") (pin "K") (pinfunction "C_K") (pintype "passive"))
    )
    (net (code "69") (name "Net-(R25-S)") (class "Default")
      (node (ref "Q1") (pin "S") (pinfunction "S_S") (pintype "passive"))
      (node (ref "R25") (pin "2") (pinfunction "S_2") (pintype "passive"))
    )
    (net (code "70") (name "Net-(R26-Pad1)") (class "Default")
      (node (ref "R26") (pin "1") (pinfunction "1_1") (pintype "passive"))
      (node (ref "TSALXX") (pin "A") (pinfunction "A_A") (pintype "passive"))
    )
    (net (code "71") (name "Net-(R28-A)") (class "Default")
      (node (ref "R28") (pin "3") (pinfunction "A_3") (pintype "passive"))
      (node (ref "TSALXX1") (pin "K") (pinfunction "C_K") (pintype "passive"))
    )
    (net (code "72") (name "Net-(R28-S)") (class "Default")
      (node (ref "Q2") (pin "S") (pinfunction "S_S") (pintype "passive"))
      (node (ref "R28") (pin "2") (pinfunction "S_2") (pintype "passive"))
    )
    (net (code "73") (name "Net-(R29-Pad1)") (class "Default")
      (node (ref "R29") (pin "1") (pinfunction "1_1") (pintype "passive"))
      (node (ref "TSALXX1") (pin "A") (pinfunction "A_A") (pintype "passive"))
    )
    (net (code "74") (name "Net-(R31-A)") (class "Default")
      (node (ref "R31") (pin "3") (pinfunction "A_3") (pintype "passive"))
      (node (ref "TSALXX2") (pin "K") (pinfunction "C_K") (pintype "passive"))
    )
    (net (code "75") (name "Net-(R31-S)") (class "Default")
      (node (ref "Q3") (pin "S") (pinfunction "S_S") (pintype "passive"))
      (node (ref "R31") (pin "2") (pinfunction "S_2") (pintype "passive"))
    )
    (net (code "76") (name "Net-(R32-Pad1)") (class "Default")
      (node (ref "R32") (pin "1") (pinfunction "1_1") (pintype "passive"))
      (node (ref "TSALXX2") (pin "A") (pinfunction "A_A") (pintype "passive"))
    )
    (net (code "77") (name "Net-(R34-A)") (class "Default")
      (node (ref "R34") (pin "3") (pinfunction "A_3") (pintype "passive"))
      (node (ref "TSALXX3") (pin "K") (pinfunction "C_K") (pintype "passive"))
    )
    (net (code "78") (name "Net-(R34-S)") (class "Default")
      (node (ref "Q4") (pin "S") (pinfunction "S_S") (pintype "passive"))
      (node (ref "R34") (pin "2") (pinfunction "S_2") (pintype "passive"))
    )
    (net (code "79") (name "Net-(R35-Pad1)") (class "Default")
      (node (ref "R35") (pin "1") (pinfunction "1_1") (pintype "passive"))
      (node (ref "TSALXX3") (pin "A") (pinfunction "A_A") (pintype "passive"))
    )
    (net (code "80") (name "Net-(S1-S)") (class "Default")
      (node (ref "R45") (pin "1") (pinfunction "1_1") (pintype "passive"))
      (node (ref "R46") (pin "1") (pinfunction "1_1") (pintype "passive"))
      (node (ref "S1") (pin "3") (pinfunction "S_3") (pintype "passive"))
    )
    (net (code "81") (name "Net-(S2-O)") (class "Default")
      (node (ref "L2") (pin "1") (pinfunction "1_1") (pintype "passive"))
      (node (ref "S2") (pin "1") (pinfunction "O_1") (pintype "passive"))
      (node (ref "U$4") (pin "4") (pinfunction "VIN_4") (pintype "bidirectional"))
    )
    (net (code "82") (name "Net-(S3-O)") (class "Default")
      (node (ref "Q3") (pin "D") (pinfunction "D_D") (pintype "passive"))
      (node (ref "S3") (pin "1") (pinfunction "O_1") (pintype "passive"))
      (node (ref "S3") (pin "2") (pinfunction "P_2") (pintype "passive"))
    )
    (net (code "83") (name "Net-(S4-O)") (class "Default")
      (node (ref "Q1") (pin "G") (pinfunction "G_G") (pintype "passive"))
      (node (ref "R23") (pin "2") (pinfunction "2_2") (pintype "passive"))
      (node (ref "S4") (pin "1") (pinfunction "O_1") (pintype "passive"))
      (node (ref "S4") (pin "2") (pinfunction "P_2") (pintype "passive"))
    )
    (net (code "84") (name "Net-(SG1-Pad-)") (class "Default")
      (node (ref "SG1") (pin "-") (pinfunction "-_-") (pintype "passive"))
      (node (ref "T1") (pin "C") (pinfunction "C_C") (pintype "passive"))
    )
    (net (code "85") (name "Net-(U$1-AREF)") (class "Default")
      (node (ref "C1") (pin "1") (pinfunction "1_1") (pintype "passive"))
      (node (ref "U$1") (pin "42") (pinfunction "AREF_42") (pintype "bidirectional"))
    )
    (net (code "86") (name "Net-(U$1-PE2{slash}~{HWB})") (class "Default")
      (node (ref "R3") (pin "2") (pinfunction "2_2") (pintype "passive"))
      (node (ref "U$1") (pin "33") (pinfunction "PE2/~{HWB}_33") (pintype "bidirectional"))
    )
    (net (code "87") (name "Net-(U$1-UCAP)") (class "Default")
      (node (ref "C6") (pin "1") (pinfunction "1_1") (pintype "passive"))
      (node (ref "U$1") (pin "6") (pinfunction "UCAP_6") (pintype "bidirectional"))
    )
    (net (code "88") (name "Net-(U$1-XTAL2)") (class "Default")
      (node (ref "C3") (pin "1") (pinfunction "1_1") (pintype "passive"))
      (node (ref "CRYSTAL") (pin "1") (pinfunction "1_1") (pintype "passive"))
      (node (ref "R1") (pin "2") (pinfunction "2_2") (pintype "passive"))
      (node (ref "U$1") (pin "16") (pinfunction "XTAL2_16") (pintype "bidirectional"))
    )
    (net (code "89") (name "Net-(U$4-FB)") (class "Default")
      (node (ref "R10") (pin "2") (pinfunction "2_2") (pintype "passive"))
      (node (ref "R11") (pin "1") (pinfunction "1_1") (pintype "passive"))
      (node (ref "U$4") (pin "5") (pinfunction "FB_5") (pintype "bidirectional"))
    )
    (net (code "90") (name "Net-(U$4-SW)") (class "Default")
      (node (ref "D2") (pin "A") (pinfunction "A_A") (pintype "passive"))
      (node (ref "L2") (pin "2") (pinfunction "2_2") (pintype "passive"))
      (node (ref "U$4") (pin "3") (pinfunction "SW_3") (pintype "bidirectional"))
    )
    (net (code "91") (name "Net-(U$11A-+IN)") (class "Default")
      (node (ref "C33") (pin "1") (pinfunction "1_1") (pintype "passive"))
      (node (ref "R43") (pin "1") (pinfunction "1_1") (pintype "passive"))
      (node (ref "R44") (pin "1") (pinfunction "1_1") (pintype "passive"))
      (node (ref "U$11") (pin "3") (pinfunction "+IN_3") (pintype "input"))
    )
    (net (code "92") (name "Net-(U$11A--IN)") (class "Default")
      (node (ref "R41") (pin "2") (pinfunction "2_2") (pintype "passive"))
      (node (ref "R42") (pin "1") (pinfunction "1_1") (pintype "passive"))
      (node (ref "U$11") (pin "2") (pinfunction "-IN_2") (pintype "input"))
    )
    (net (code "93") (name "VIN") (class "Default")
      (node (ref "C10") (pin "+") (pinfunction "+_+") (pintype "passive"))
      (node (ref "C21") (pin "2") (pinfunction "2_2") (pintype "passive"))
    )
    (net (code "94") (name "V_BATT") (class "Default")
      (node (ref "C12") (pin "+") (pinfunction "+_+") (pintype "passive"))
      (node (ref "C13") (pin "A") (pinfunction "+_A") (pintype "passive"))
      (node (ref "C14") (pin "1") (pinfunction "1_1") (pintype "passive"))
      (node (ref "C16") (pin "A") (pinfunction "+_A") (pintype "passive"))
      (node (ref "C22") (pin "2") (pinfunction "2_2") (pintype "passive"))
      (node (ref "D2") (pin "C") (pinfunction "C_C") (pintype "passive"))
      (node (ref "R10") (pin "1") (pinfunction "1_1") (pintype "passive"))
      (node (ref "U$5") (pin "3") (pinfunction "VIN_3") (pintype "bidirectional"))
      (node (ref "U1") (pin "13") (pinfunction "VM2_13") (pintype "bidirectional"))
      (node (ref "U1") (pin "14") (pinfunction "VM3_14") (pintype "bidirectional"))
      (node (ref "U1") (pin "24") (pinfunction "VM1_24") (pintype "bidirectional"))
    )
    (net (code "95") (name "unconnected-(IC1-DIS-Pad7)") (class "Default")
      (node (ref "IC1") (pin "7") (pinfunction "DIS_7") (pintype "input"))
    )
    (net (code "96") (name "unconnected-(R24-E-Pad1)") (class "Default")
      (node (ref "R24") (pin "1") (pinfunction "E_1") (pintype "passive"))
    )
    (net (code "97") (name "unconnected-(R25-E-Pad1)") (class "Default")
      (node (ref "R25") (pin "1") (pinfunction "E_1") (pintype "passive"))
    )
    (net (code "98") (name "unconnected-(R28-E-Pad1)") (class "Default")
      (node (ref "R28") (pin "1") (pinfunction "E_1") (pintype "passive"))
    )
    (net (code "99") (name "unconnected-(R31-E-Pad1)") (class "Default")
      (node (ref "R31") (pin "1") (pinfunction "E_1") (pintype "passive"))
    )
    (net (code "100") (name "unconnected-(R34-E-Pad1)") (class "Default")
      (node (ref "R34") (pin "1") (pinfunction "E_1") (pintype "passive"))
    )
    (net (code "101") (name "unconnected-(U$4-EN-Pad2)") (class "Default")
      (node (ref "U$4") (pin "2") (pinfunction "EN_2") (pintype "bidirectional"))
    )
  )
)
